# I2C_Shield.net
KiCad netlist of a schematic drawn in Altium Designer
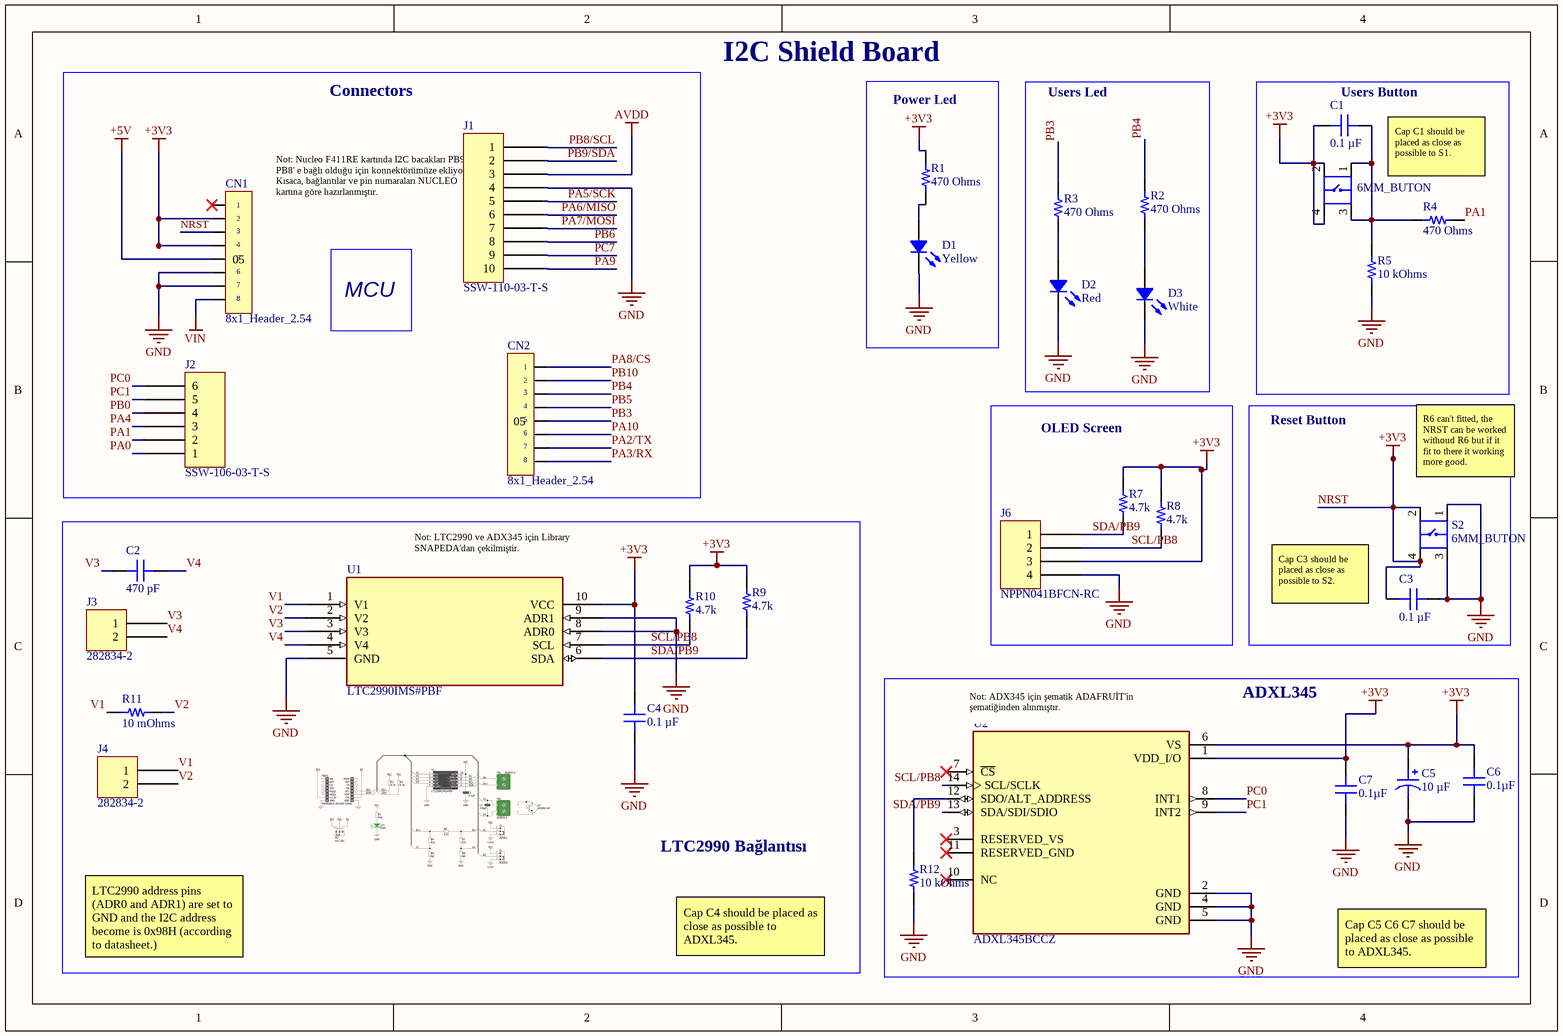
[diagram p0: I2C_Shield.SchDoc]

(export (version "E")
  (design (tool "Eeschema 10.0.6"))
  (components
    (comp (ref "C1")
      (value "0.1 µF")
      (footprint "CAP 0805_2012")
      (description "CAP CER 0.1UF 16V X7R 0805")
      (fields
        (field (name "PART NUMBER") "0805B104K160CT")
        (field (name "CAPACITANCE") "0.1 µF")
        (field (name "MANUFACTURER") "Walsin Technology Corporation")
      )
      (libsource (lib "Lib") (part "Capacitor"))
    )
    (comp (ref "C2")
      (value "470 pF")
      (footprint "CAP 0805_2012")
      (description "CAP CER 470PF 10V X7R 0805")
      (fields
        (field (name "PART NUMBER") "885012207006")
        (field (name "CAPACITANCE") "470 pF")
        (field (name "MANUFACTURER") "Würth Elektronik")
      )
      (libsource (lib "Lib") (part "Capacitor"))
    )
    (comp (ref "C3")
      (value "0.1 µF")
      (footprint "CAP 0805_2012")
      (description "CAP CER 0.1UF 16V X7R 0805")
      (fields
        (field (name "PART NUMBER") "0805B104K160CT")
        (field (name "MANUFACTURER") "Walsin Technology Corporation")
      )
      (libsource (lib "Lib") (part "Capacitor"))
    )
    (comp (ref "C4")
      (value "0.1 µF")
      (footprint "CAP 0805_2012")
      (description "CAP CER 0.1UF 10V 0805")
      (fields
        (field (name "PART NUMBER") "LMK212SD104KG-T")
        (field (name "CAPACITANCE") "0.1 µF")
        (field (name "MANUFACTURER") "Taiyo Yuden")
      )
      (libsource (lib "Lib") (part "Capacitor"))
    )
    (comp (ref "C5")
      (value "10 µF")
      (footprint "CAP POL 1206_3216")
      (description "CAP TANT 10UF 10% 10V 1206")
      (fields (field (name "PART NUMBER") "593D106X9010A2TE3") (field (name "MANUFACTURER") "Vishay Sprague"))
      (libsource (lib "Lib") (part "Polarised Capacitor"))
    )
    (comp (ref "C6")
      (value "0.1µF")
      (footprint "CAP 0805_2012")
      (description "CAP CER 0.1UF 25V X7R 0805")
      (fields
        (field (name "PART NUMBER") "08053C104JAT4A")
        (field (name "CAPACITANCE") "0.1µF")
        (field (name "MANUFACTURER") "AVX Corporation")
      )
      (libsource (lib "Lib") (part "Capacitor"))
    )
    (comp (ref "C7")
      (value "0.1µF")
      (footprint "CAP 0805_2012")
      (description "CAP CER 0.1UF 25V X7R 0805")
      (fields
        (field (name "PART NUMBER") "08053C104JAT4A")
        (field (name "CAPACITANCE") "0.1µF")
        (field (name "MANUFACTURER") "AVX Corporation")
      )
      (libsource (lib "Lib") (part "Capacitor"))
    )
    (comp (ref "CN1")
      (value "8x1_Header_2.54")
      (footprint "8X1_HEADER")
      (libsource (lib "I2C_Shield") (part "8x1_Header_2.54"))
    )
    (comp (ref "CN2")
      (value "8x1_Header_2.54")
      (footprint "8X1_HEADER")
      (libsource (lib "") (part "8x1_Header_2.54_1"))
    )
    (comp (ref "D1")
      (value "Yellow")
      (footprint "LED 0805_2012 YELLOW")
      (description "LED YELLOW 0805 SMD")
      (fields (field (name "PART NUMBER") "5975406507F") (field (name "MANUFACTURER") "Dialight"))
      (libsource (lib "Lib") (part "LED"))
    )
    (comp (ref "D2")
      (value "Red")
      (footprint "LED 0805_2012 RED")
      (description "LED RED DIFFUSED 0805 SMD")
      (fields
        (field (name "PART NUMBER") "LS R976-NR-1")
        (field (name "MANUFACTURER") "OSRAM Opto Semiconductors Inc.")
      )
      (libsource (lib "Lib") (part "LED"))
    )
    (comp (ref "D3")
      (value "White")
      (footprint "LED 0805_2012")
      (description "LED WHITE 0805 SMD")
      (fields
        (field (name "PART NUMBER") "B1701TX--20P000614U1930")
        (field (name "MANUFACTURER") "Harvatek Corporation")
      )
      (libsource (lib "Lib") (part "LED"))
    )
    (comp (ref "J1")
      (value "SSW-110-03-T-S")
      (footprint "SAMTEC SSW-110-03-T-S")
      (description "CONN RCPT 10POS 0.1 TIN PCB")
      (fields (field (name "MANUFACTURER") "Samtec Inc."))
      (libsource (lib "Lib") (part "10 Pin"))
    )
    (comp (ref "J2")
      (value "SSW-106-03-T-S")
      (footprint "SAMTEC SSW-106-03-T-S")
      (description "CONN RCPT 6POS 0.1 TIN PCB")
      (fields (field (name "MANUFACTURER") "Samtec Inc."))
      (libsource (lib "Lib") (part "6 Pin"))
    )
    (comp (ref "J3")
      (value "282834-2")
      (footprint "TE 282834-2")
      (description "TERM BLK 2P SIDE ENT 2.54MM PCB")
      (fields (field (name "MANUFACTURER") "TE Connectivity AMP Connectors") (field (name "VOLTAGE") "150V"))
      (libsource (lib "Lib") (part "2 Pin"))
    )
    (comp (ref "J4")
      (value "282834-2")
      (footprint "TE 282834-2")
      (description "TERM BLK 2P SIDE ENT 2.54MM PCB")
      (fields (field (name "MANUFACTURER") "TE Connectivity AMP Connectors") (field (name "VOLTAGE") "150V"))
      (libsource (lib "Lib") (part "2 Pin"))
    )
    (comp (ref "J6")
      (value "NPPN041BFCN-RC")
      (footprint "SULLINS NPPN041BFCN")
      (description "CONN HDR 4POS 0.079 GOLD PCB")
      (fields (field (name "MANUFACTURER") "Sullins Connector Solutions"))
      (libsource (lib "Lib") (part "4 Pin"))
    )
    (comp (ref "R1")
      (value "470 Ohms")
      (footprint "YAGEO RES RK73 RS73 SG73 0805_2012")
      (description "RES 470 OHM 0.5% 1/8W 0805")
      (fields
        (field (name "PART NUMBER") "RK73G2ARTTD4700D")
        (field (name "MANUFACTURER") "KOA Speer Electronics, Inc.")
      )
      (libsource (lib "Lib") (part "Resistor"))
    )
    (comp (ref "R2")
      (value "470 Ohms")
      (footprint "YAGEO RES RK73 RS73 SG73 0805_2012")
      (description "RES 470 OHM 0.5% 1/8W 0805")
      (fields
        (field (name "PART NUMBER") "RK73G2ARTTD4700D")
        (field (name "MANUFACTURER") "KOA Speer Electronics, Inc.")
      )
      (libsource (lib "Lib") (part "Resistor"))
    )
    (comp (ref "R3")
      (value "470 Ohms")
      (footprint "YAGEO RES RK73 RS73 SG73 0805_2012")
      (description "RES 470 OHM 0.5% 1/8W 0805")
      (fields
        (field (name "PART NUMBER") "RK73G2ARTTD4700D")
        (field (name "MANUFACTURER") "KOA Speer Electronics, Inc.")
      )
      (libsource (lib "Lib") (part "Resistor"))
    )
    (comp (ref "R4")
      (value "470 Ohms")
      (footprint "YAGEO RES RK73 RS73 SG73 0805_2012")
      (description "RES 470 OHM 0.5% 1/8W 0805")
      (fields
        (field (name "PART NUMBER") "RK73G2ARTTD4700D")
        (field (name "MANUFACTURER") "KOA Speer Electronics, Inc.")
      )
      (libsource (lib "Lib") (part "Resistor"))
    )
    (comp (ref "R5")
      (value "10 kOhms")
      (footprint "RES 0805_2012")
      (description "RES 10K OHM 0.1% 1/10W 0805")
      (fields
        (field (name "PART NUMBER") "RNCS0805BKE10K0")
        (field (name "MANUFACTURER") "Stackpole Electronics Inc")
      )
      (libsource (lib "Lib") (part "Resistor"))
    )
    (comp (ref "R7")
      (value "4.7k")
      (footprint "RES 0805_2012")
      (description "RES SMD 4.7K OHM 5% 1/2W 0805")
      (fields (field (name "PART NUMBER") "RCS08054K70JNEA") (field (name "MANUFACTURER") "Vishay Dale"))
      (libsource (lib "Lib") (part "Resistor"))
    )
    (comp (ref "R8")
      (value "4.7k")
      (footprint "RES 0805_2012")
      (description "RES SMD 4.7K OHM 5% 1/2W 0805")
      (fields (field (name "PART NUMBER") "RCS08054K70JNEA") (field (name "MANUFACTURER") "Vishay Dale"))
      (libsource (lib "Lib") (part "Resistor"))
    )
    (comp (ref "R9")
      (value "4.7k")
      (footprint "RES 0805_2012")
      (description "RES SMD 4.7K OHM 5% 1/2W 0805")
      (fields (field (name "PART NUMBER") "RCS08054K70JNEA") (field (name "MANUFACTURER") "Vishay Dale"))
      (libsource (lib "Lib") (part "Resistor"))
    )
    (comp (ref "R10")
      (value "4.7k")
      (footprint "RES 0805_2012")
      (description "RES SMD 4.7K OHM 5% 1/2W 0805")
      (fields (field (name "PART NUMBER") "RCS08054K70JNEA") (field (name "MANUFACTURER") "Vishay Dale"))
      (libsource (lib "Lib") (part "Resistor"))
    )
    (comp (ref "R11")
      (value "10 mOhms")
      (footprint "RES 0805_2012")
      (description "RES 0.01 OHM 1% 1/2W 0805")
      (fields
        (field (name "PART NUMBER") "CSRF0805FT10L0")
        (field (name "MANUFACTURER") "Stackpole Electronics Inc")
      )
      (libsource (lib "Lib") (part "Resistor"))
    )
    (comp (ref "R12")
      (value "10 kOhms")
      (footprint "RES 0805_2012")
      (description "RES 10K OHM 0.1% 1/10W 0805")
      (fields
        (field (name "PART NUMBER") "RNCS0805BKE10K0")
        (field (name "MANUFACTURER") "Stackpole Electronics Inc")
      )
      (libsource (lib "Lib") (part "Resistor"))
    )
    (comp (ref "S1")
      (value "6MM_BUTON")
      (footprint "6MMTACTILESWITCH")
      (description "SWITCH TACT 6x6MM")
      (libsource (lib "I2C_Shield") (part "6MM_BUTON"))
    )
    (comp (ref "S2")
      (value "6MM_BUTON")
      (footprint "6MMTACTILESWITCH")
      (description "SWITCH TACT 6x6MM")
      (libsource (lib "I2C_Shield") (part "6MM_BUTON"))
    )
    (comp (ref "U1")
      (value "LTC2990IMS#PBF")
      (footprint "MSOP-10_MS")
      (description "Quad I2C Voltage, Current and Temperature Monitor")
      (fields (field (name "MF") "Analog Devices"))
      (libsource (lib "LTC2990IMS_PBF") (part "LTC2990IMS#PBF"))
    )
    (comp (ref "U2")
      (value "ADXL345BCCZ")
      (footprint "IC_ADXL345BCCZ")
      (description "3-Axis, Â±2 g/Â±4 g/Â±8 g/Â±16 g Digital Accelerometer")
      (fields (field (name "MF") "Analog Devices"))
      (libsource (lib "ADXL345BCCZ") (part "ADXL345BCCZ"))
    )
  )
  (nets
    (net (code "1") (name "+3V3") (class "Default")
      (node (ref "C1") (pin "1") (pinfunction "1_1") (pintype "passive"))
      (node (ref "C3") (pin "1") (pinfunction "1_1") (pintype "passive"))
      (node (ref "C4") (pin "1") (pinfunction "1_1") (pintype "passive"))
      (node (ref "C5") (pin "1") (pinfunction "1_1") (pintype "passive"))
      (node (ref "C6") (pin "1") (pinfunction "1_1") (pintype "passive"))
      (node (ref "C7") (pin "1") (pinfunction "1_1") (pintype "passive"))
      (node (ref "CN1") (pin "02") (pinfunction "02_02") (pintype "passive"))
      (node (ref "CN1") (pin "03") (pinfunction "03_03") (pintype "passive"))
      (node (ref "CN1") (pin "04") (pinfunction "04_04") (pintype "passive"))
      (node (ref "J6") (pin "3") (pinfunction "3_3") (pintype "passive"))
      (node (ref "R1") (pin "1") (pinfunction "1_1") (pintype "passive"))
      (node (ref "R10") (pin "1") (pinfunction "1_1") (pintype "passive"))
      (node (ref "R7") (pin "1") (pinfunction "1_1") (pintype "passive"))
      (node (ref "R8") (pin "1") (pinfunction "1_1") (pintype "passive"))
      (node (ref "R9") (pin "1") (pinfunction "1_1") (pintype "passive"))
      (node (ref "S1") (pin "2") (pinfunction "2_2") (pintype "passive"))
      (node (ref "S1") (pin "4") (pinfunction "4_4") (pintype "passive"))
      (node (ref "S2") (pin "2") (pinfunction "2_2") (pintype "passive"))
      (node (ref "S2") (pin "4") (pinfunction "4_4") (pintype "passive"))
      (node (ref "U1") (pin "10") (pinfunction "VCC_10") (pintype "power_in"))
      (node (ref "U2") (pin "1") (pinfunction "VDD_I/O_1") (pintype "power_in"))
      (node (ref "U2") (pin "6") (pinfunction "VS_6") (pintype "power_in"))
    )
    (net (code "2") (name "+5V") (class "Default")
      (node (ref "CN1") (pin "05") (pinfunction "05_05") (pintype "passive"))
    )
    (net (code "3") (name "/PA0") (class "Default")
      (node (ref "J2") (pin "1") (pinfunction "1_1") (pintype "passive"))
    )
    (net (code "4") (name "/PA1") (class "Default")
      (node (ref "J2") (pin "2") (pinfunction "2_2") (pintype "passive"))
      (node (ref "R4") (pin "1") (pinfunction "1_1") (pintype "passive"))
    )
    (net (code "5") (name "/PA2{slash}TX") (class "Default")
      (node (ref "CN2") (pin "07") (pinfunction "07_07") (pintype "passive"))
    )
    (net (code "6") (name "/PA3{slash}RX") (class "Default")
      (node (ref "CN2") (pin "08") (pinfunction "08_08") (pintype "passive"))
    )
    (net (code "7") (name "/PA4") (class "Default")
      (node (ref "J2") (pin "3") (pinfunction "3_3") (pintype "passive"))
    )
    (net (code "8") (name "/PA5{slash}SCK") (class "Default")
      (node (ref "J1") (pin "5") (pinfunction "5_5") (pintype "passive"))
    )
    (net (code "9") (name "/PA6{slash}MISO") (class "Default")
      (node (ref "J1") (pin "6") (pinfunction "6_6") (pintype "passive"))
    )
    (net (code "10") (name "/PA7{slash}MOSI") (class "Default")
      (node (ref "J1") (pin "7") (pinfunction "7_7") (pintype "passive"))
    )
    (net (code "11") (name "/PA8{slash}CS") (class "Default")
      (node (ref "CN2") (pin "01") (pinfunction "01_01") (pintype "passive"))
    )
    (net (code "12") (name "/PA9") (class "Default")
      (node (ref "J1") (pin "10") (pinfunction "10_10") (pintype "passive"))
    )
    (net (code "13") (name "/PA10") (class "Default")
      (node (ref "CN2") (pin "06") (pinfunction "06_06") (pintype "passive"))
    )
    (net (code "14") (name "/PB0") (class "Default")
      (node (ref "J2") (pin "4") (pinfunction "4_4") (pintype "passive"))
    )
    (net (code "15") (name "/PB3") (class "Default")
      (node (ref "CN2") (pin "05") (pinfunction "05_05") (pintype "passive"))
      (node (ref "R3") (pin "1") (pinfunction "1_1") (pintype "passive"))
    )
    (net (code "16") (name "/PB4") (class "Default")
      (node (ref "CN2") (pin "03") (pinfunction "03_03") (pintype "passive"))
      (node (ref "R2") (pin "1") (pinfunction "1_1") (pintype "passive"))
    )
    (net (code "17") (name "/PB5") (class "Default")
      (node (ref "CN2") (pin "04") (pinfunction "04_04") (pintype "passive"))
    )
    (net (code "18") (name "/PB6") (class "Default")
      (node (ref "J1") (pin "8") (pinfunction "8_8") (pintype "passive"))
    )
    (net (code "19") (name "/PB8{slash}SCL") (class "Default")
      (node (ref "J1") (pin "1") (pinfunction "1_1") (pintype "passive"))
    )
    (net (code "20") (name "/PB9{slash}SDA") (class "Default")
      (node (ref "J1") (pin "2") (pinfunction "2_2") (pintype "passive"))
    )
    (net (code "21") (name "/PB10") (class "Default")
      (node (ref "CN2") (pin "02") (pinfunction "02_02") (pintype "passive"))
    )
    (net (code "22") (name "/PC0") (class "Default")
      (node (ref "J2") (pin "6") (pinfunction "6_6") (pintype "passive"))
      (node (ref "U2") (pin "8") (pinfunction "INT1_8") (pintype "output"))
    )
    (net (code "23") (name "/PC1") (class "Default")
      (node (ref "J2") (pin "5") (pinfunction "5_5") (pintype "passive"))
      (node (ref "U2") (pin "9") (pinfunction "INT2_9") (pintype "output"))
    )
    (net (code "24") (name "/PC7") (class "Default")
      (node (ref "J1") (pin "9") (pinfunction "9_9") (pintype "passive"))
    )
    (net (code "25") (name "/SCL{slash}PB8") (class "Default")
      (node (ref "J6") (pin "2") (pinfunction "2_2") (pintype "passive"))
      (node (ref "R10") (pin "2") (pinfunction "2_2") (pintype "passive"))
      (node (ref "R8") (pin "2") (pinfunction "2_2") (pintype "passive"))
      (node (ref "U1") (pin "7") (pinfunction "SCL_7") (pintype "input"))
      (node (ref "U2") (pin "14") (pinfunction "SCL/SCLK_14") (pintype "input"))
    )
    (net (code "26") (name "/SDA{slash}PB9") (class "Default")
      (node (ref "J6") (pin "1") (pinfunction "1_1") (pintype "passive"))
      (node (ref "R7") (pin "2") (pinfunction "2_2") (pintype "passive"))
      (node (ref "R9") (pin "2") (pinfunction "2_2") (pintype "passive"))
      (node (ref "U1") (pin "6") (pinfunction "SDA_6") (pintype "bidirectional"))
      (node (ref "U2") (pin "13") (pinfunction "SDA/SDI/SDIO_13") (pintype "bidirectional"))
    )
    (net (code "27") (name "/V1") (class "Default")
      (node (ref "J4") (pin "1") (pinfunction "1_1") (pintype "passive"))
      (node (ref "R11") (pin "1") (pinfunction "1_1") (pintype "passive"))
      (node (ref "U1") (pin "1") (pinfunction "V1_1") (pintype "input"))
    )
    (net (code "28") (name "/V2") (class "Default")
      (node (ref "J4") (pin "2") (pinfunction "2_2") (pintype "passive"))
      (node (ref "R11") (pin "2") (pinfunction "2_2") (pintype "passive"))
      (node (ref "U1") (pin "2") (pinfunction "V2_2") (pintype "input"))
    )
    (net (code "29") (name "/V3") (class "Default")
      (node (ref "C2") (pin "1") (pinfunction "1_1") (pintype "passive"))
      (node (ref "J3") (pin "1") (pinfunction "1_1") (pintype "passive"))
      (node (ref "U1") (pin "3") (pinfunction "V3_3") (pintype "input"))
    )
    (net (code "30") (name "/V4") (class "Default")
      (node (ref "C2") (pin "2") (pinfunction "2_2") (pintype "passive"))
      (node (ref "J3") (pin "2") (pinfunction "2_2") (pintype "passive"))
      (node (ref "U1") (pin "4") (pinfunction "V4_4") (pintype "input"))
    )
    (net (code "31") (name "AVDD") (class "Default")
      (node (ref "J1") (pin "3") (pinfunction "3_3") (pintype "passive"))
    )
    (net (code "32") (name "GND") (class "Default")
      (node (ref "C3") (pin "2") (pinfunction "2_2") (pintype "passive"))
      (node (ref "C4") (pin "2") (pinfunction "2_2") (pintype "passive"))
      (node (ref "C5") (pin "2") (pinfunction "2_2") (pintype "passive"))
      (node (ref "C6") (pin "2") (pinfunction "2_2") (pintype "passive"))
      (node (ref "C7") (pin "2") (pinfunction "2_2") (pintype "passive"))
      (node (ref "CN1") (pin "06") (pinfunction "06_06") (pintype "passive"))
      (node (ref "CN1") (pin "07") (pinfunction "07_07") (pintype "passive"))
      (node (ref "D1") (pin "2") (pinfunction "2_2") (pintype "passive"))
      (node (ref "D2") (pin "2") (pinfunction "2_2") (pintype "passive"))
      (node (ref "D3") (pin "2") (pinfunction "2_2") (pintype "passive"))
      (node (ref "J1") (pin "4") (pinfunction "4_4") (pintype "passive"))
      (node (ref "J6") (pin "4") (pinfunction "4_4") (pintype "passive"))
      (node (ref "R12") (pin "2") (pinfunction "2_2") (pintype "passive"))
      (node (ref "R5") (pin "2") (pinfunction "2_2") (pintype "passive"))
      (node (ref "S2") (pin "1") (pinfunction "1_1") (pintype "passive"))
      (node (ref "S2") (pin "3") (pinfunction "3_3") (pintype "passive"))
      (node (ref "U1") (pin "5") (pinfunction "GND_5") (pintype "power_in"))
      (node (ref "U1") (pin "8") (pinfunction "ADR0_8") (pintype "input"))
      (node (ref "U1") (pin "9") (pinfunction "ADR1_9") (pintype "input"))
      (node (ref "U2") (pin "2") (pinfunction "GND_2") (pintype "power_in"))
      (node (ref "U2") (pin "4") (pinfunction "GND_4") (pintype "power_in"))
      (node (ref "U2") (pin "5") (pinfunction "GND_5") (pintype "power_in"))
    )
    (net (code "33") (name "Net-(C1-Pad2)") (class "Default")
      (node (ref "C1") (pin "2") (pinfunction "2_2") (pintype "passive"))
      (node (ref "R4") (pin "2") (pinfunction "2_2") (pintype "passive"))
      (node (ref "R5") (pin "1") (pinfunction "1_1") (pintype "passive"))
      (node (ref "S1") (pin "1") (pinfunction "1_1") (pintype "passive"))
      (node (ref "S1") (pin "3") (pinfunction "3_3") (pintype "passive"))
    )
    (net (code "34") (name "Net-(D1-Pad1)") (class "Default")
      (node (ref "D1") (pin "1") (pinfunction "1_1") (pintype "passive"))
      (node (ref "R1") (pin "2") (pinfunction "2_2") (pintype "passive"))
    )
    (net (code "35") (name "Net-(D2-Pad1)") (class "Default")
      (node (ref "D2") (pin "1") (pinfunction "1_1") (pintype "passive"))
      (node (ref "R3") (pin "2") (pinfunction "2_2") (pintype "passive"))
    )
    (net (code "36") (name "Net-(D3-Pad1)") (class "Default")
      (node (ref "D3") (pin "1") (pinfunction "1_1") (pintype "passive"))
      (node (ref "R2") (pin "2") (pinfunction "2_2") (pintype "passive"))
    )
    (net (code "37") (name "Net-(U2-SDO{slash}ALT_ADDRESS)") (class "Default")
      (node (ref "R12") (pin "1") (pinfunction "1_1") (pintype "passive"))
      (node (ref "U2") (pin "12") (pinfunction "SDO/ALT_ADDRESS_12") (pintype "bidirectional"))
    )
    (net (code "38") (name "VIN") (class "Default")
      (node (ref "CN1") (pin "08") (pinfunction "08_08") (pintype "passive"))
    )
    (net (code "39") (name "unconnected-(CN1-Pad01)") (class "Default")
      (node (ref "CN1") (pin "01") (pinfunction "01_01") (pintype "passive+no_connect"))
    )
    (net (code "40") (name "unconnected-(U2-NC-Pad10)") (class "Default")
      (node (ref "U2") (pin "10") (pinfunction "NC_10") (pintype "passive+no_connect"))
    )
    (net (code "41") (name "unconnected-(U2-RESERVED_GND-Pad11)") (class "Default")
      (node (ref "U2") (pin "11") (pinfunction "RESERVED_GND_11") (pintype "passive+no_connect"))
    )
    (net (code "42") (name "unconnected-(U2-RESERVED_VS-Pad3)") (class "Default")
      (node (ref "U2") (pin "3") (pinfunction "RESERVED_VS_3") (pintype "passive+no_connect"))
    )
    (net (code "43") (name "unconnected-(U2-~{CS}-Pad7)") (class "Default")
      (node (ref "U2") (pin "7") (pinfunction "~{CS}_7") (pintype "input+no_connect"))
    )
  )
)
